# 3K_valdiklis_v1_2.net
KiCad netlist of a schematic drawn in EAGLE
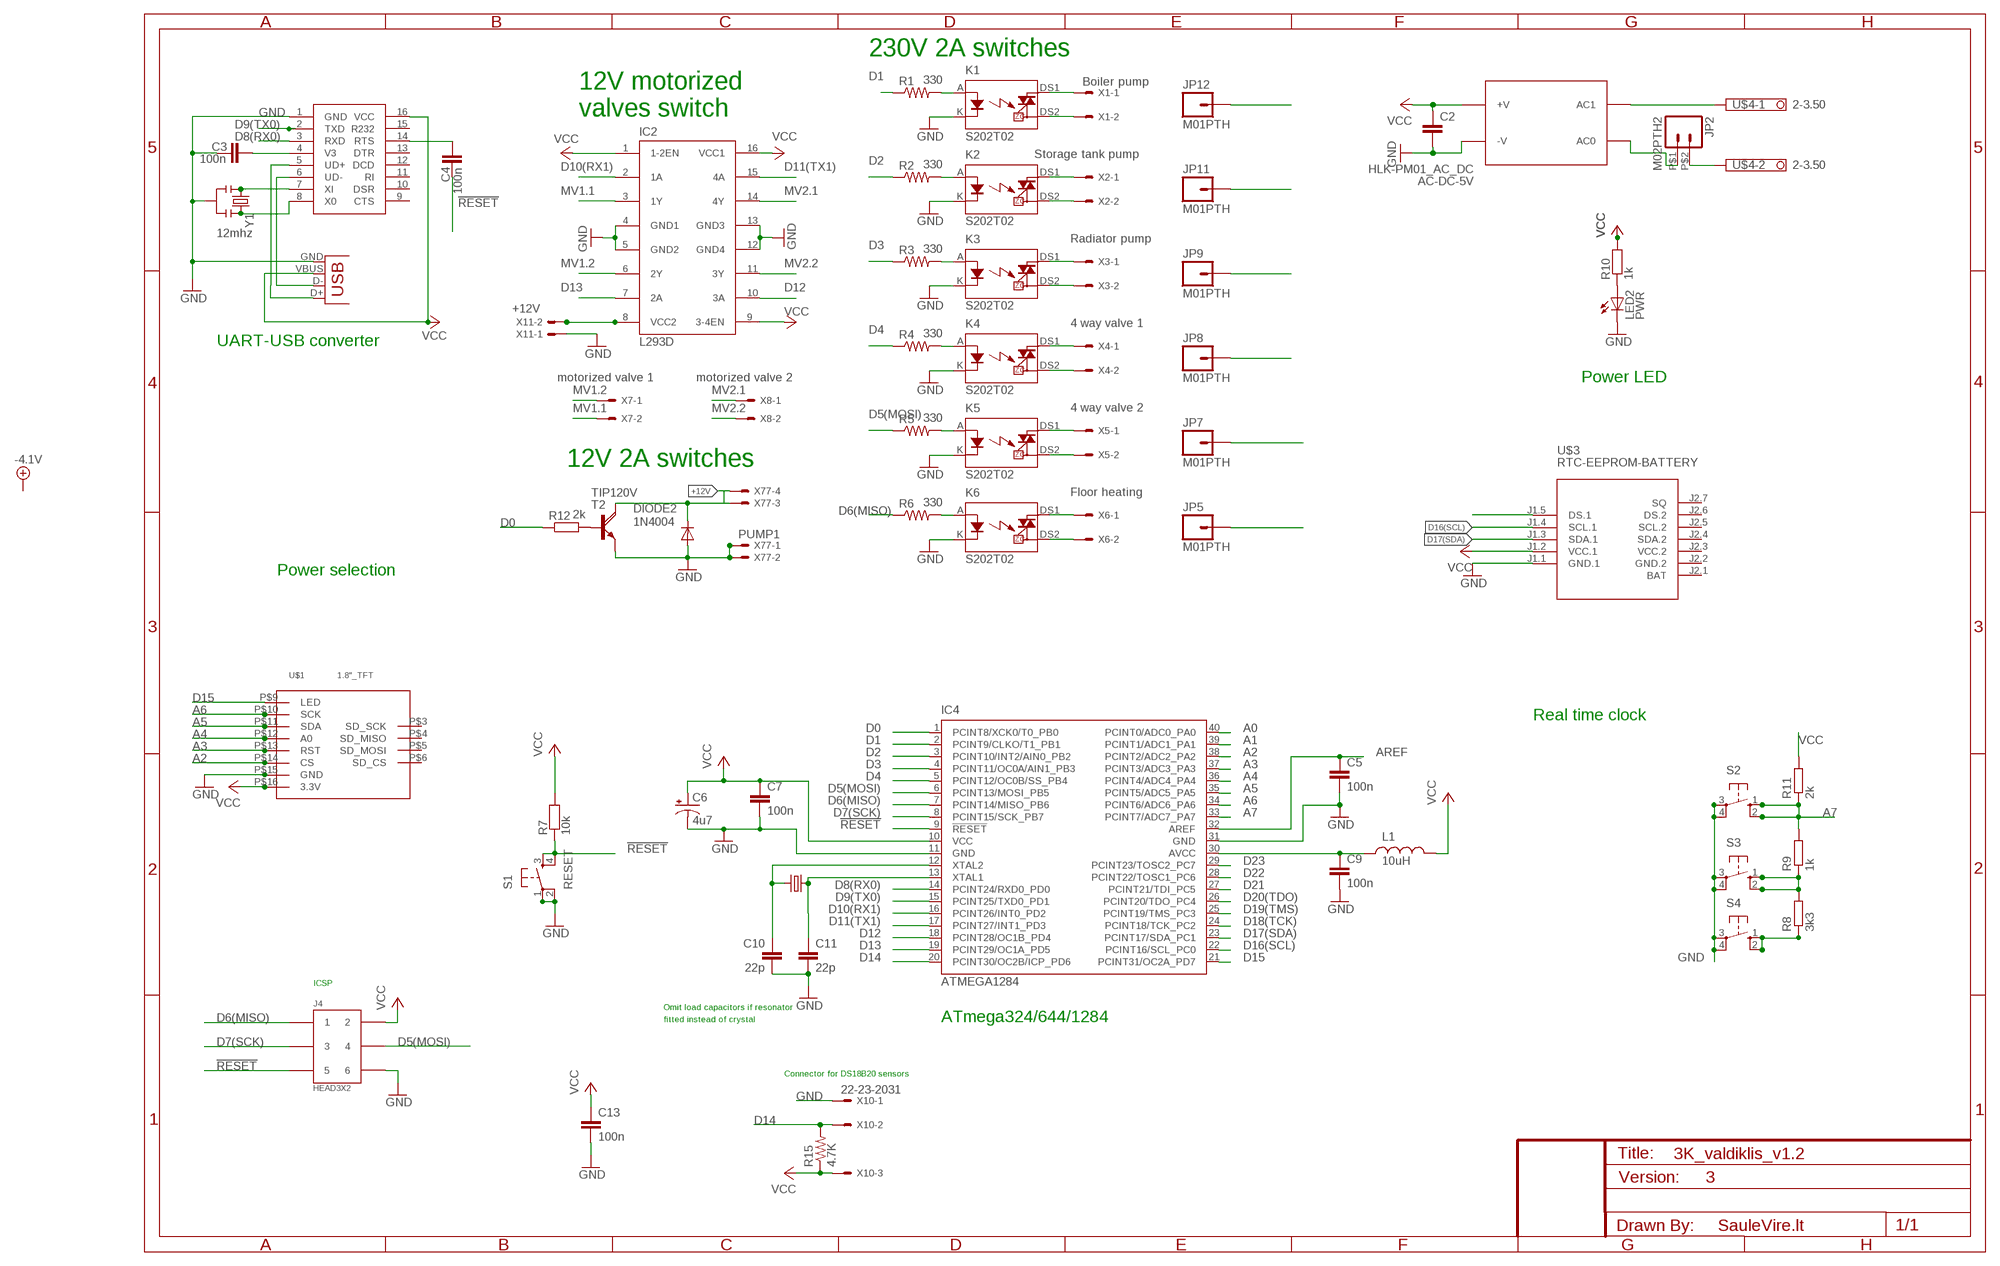
[diagram p0: schematic, sheet 1]

(export (version "E")
  (design (tool "Eeschema 10.0.6"))
  (components
    (comp (ref "AC-DC-5V")
      (value "HLK-PM01_AC_DC")
      (footprint "eagle-import:HLK-PM01_AC_DC")
      (libsource (lib "eagle-import") (part "HLK-PM01_AC_DC"))
    )
    (comp (ref "C2")
      (value "C-EU025-024X044")
      (footprint "eagle-import:C025-024X044")
      (libsource (lib "eagle-import") (part "C-EU025-024X044"))
    )
    (comp (ref "C3")
      (value "100n")
      (footprint "eagle-import:CAP-PTH-SMALL")
      (libsource (lib "eagle-import") (part "CAPPTH"))
    )
    (comp (ref "C4")
      (value "100n")
      (footprint "eagle-import:CAP-PTH-SMALL")
      (libsource (lib "eagle-import") (part "CAPPTH"))
    )
    (comp (ref "C5")
      (value "100n")
      (footprint "eagle-import:CAP-PTH-SMALL")
      (libsource (lib "eagle-import") (part "CAPPTH"))
    )
    (comp (ref "C6")
      (value "4u7")
      (footprint "eagle-import:CPOL-RADIAL-10UF-25V")
      (libsource (lib "eagle-import") (part "CAP_POLPTH2"))
    )
    (comp (ref "C7")
      (value "100n")
      (footprint "eagle-import:CAP-PTH-SMALL")
      (libsource (lib "eagle-import") (part "CAPPTH"))
    )
    (comp (ref "C9")
      (value "100n")
      (footprint "eagle-import:CAP-PTH-SMALL")
      (libsource (lib "eagle-import") (part "CAPPTH"))
    )
    (comp (ref "C10")
      (value "22p")
      (footprint "eagle-import:CAP-PTH-SMALL")
      (libsource (lib "eagle-import") (part "CAPPTH"))
    )
    (comp (ref "C11")
      (value "22p")
      (footprint "eagle-import:CAP-PTH-SMALL")
      (libsource (lib "eagle-import") (part "CAPPTH"))
    )
    (comp (ref "C13")
      (value "100n")
      (footprint "eagle-import:CAP-PTH-SMALL")
      (libsource (lib "eagle-import") (part "CAPPTH"))
    )
    (comp (ref "DIODE2")
      (value "1N4004")
      (footprint "eagle-import:DO41-10")
      (libsource (lib "eagle-import") (part "1N4004"))
    )
    (comp (ref "IC2")
      (value "L293D")
      (footprint "eagle-import:DIL16")
      (libsource (lib "eagle-import") (part "L293D"))
    )
    (comp (ref "IC4")
      (value "ATMEGA1284")
      (footprint "eagle-import:DIL40")
      (fields (field (name "MPN") "ATMEGA644-20PU"))
      (libsource (lib "eagle-import") (part "ATMEGA644-PU20"))
    )
    (comp (ref "J4")
      (value "HEAD3X2")
      (footprint "eagle-import:HEAD3X2")
      (libsource (lib "eagle-import") (part "HEAD3X2"))
    )
    (comp (ref "JP2")
      (value "M02PTH2")
      (footprint "eagle-import:1X02_BIG")
      (libsource (lib "eagle-import") (part "M02PTH2"))
    )
    (comp (ref "JP3")
      (value "USB-B")
      (footprint "eagle-import:USB-B-PTH")
      (libsource (lib "eagle-import") (part "USBPTH"))
    )
    (comp (ref "JP5")
      (value "M01PTH")
      (footprint "eagle-import:1X01")
      (libsource (lib "eagle-import") (part "M01PTH"))
    )
    (comp (ref "JP7")
      (value "M01PTH")
      (footprint "eagle-import:1X01")
      (libsource (lib "eagle-import") (part "M01PTH"))
    )
    (comp (ref "JP8")
      (value "M01PTH")
      (footprint "eagle-import:1X01")
      (libsource (lib "eagle-import") (part "M01PTH"))
    )
    (comp (ref "JP9")
      (value "M01PTH")
      (footprint "eagle-import:1X01")
      (libsource (lib "eagle-import") (part "M01PTH"))
    )
    (comp (ref "JP11")
      (value "M01PTH")
      (footprint "eagle-import:1X01")
      (libsource (lib "eagle-import") (part "M01PTH"))
    )
    (comp (ref "JP12")
      (value "M01PTH")
      (footprint "eagle-import:1X01")
      (libsource (lib "eagle-import") (part "M01PTH"))
    )
    (comp (ref "K1")
      (value "S202T02")
      (footprint "eagle-import:S202T02")
      (libsource (lib "eagle-import") (part "S202T02"))
    )
    (comp (ref "K2")
      (value "S202T02")
      (footprint "eagle-import:S202T02")
      (libsource (lib "eagle-import") (part "S202T02"))
    )
    (comp (ref "K3")
      (value "S202T02")
      (footprint "eagle-import:S202T02")
      (libsource (lib "eagle-import") (part "S202T02"))
    )
    (comp (ref "K4")
      (value "S202T02")
      (footprint "eagle-import:S202T02")
      (libsource (lib "eagle-import") (part "S202T02"))
    )
    (comp (ref "K5")
      (value "S202T02")
      (footprint "eagle-import:S202T02")
      (libsource (lib "eagle-import") (part "S202T02"))
    )
    (comp (ref "K6")
      (value "S202T02")
      (footprint "eagle-import:S202T02")
      (libsource (lib "eagle-import") (part "S202T02"))
    )
    (comp (ref "L1")
      (value "10uH")
      (footprint "eagle-import:RES-AXIAL-0.4")
      (libsource (lib "eagle-import") (part "INDUCTOR0.4{dblquote}-AXIAL"))
    )
    (comp (ref "LED2")
      (value "PWR")
      (footprint "eagle-import:LED3MM")
      (libsource (lib "eagle-import") (part "LED3MM"))
    )
    (comp (ref "R1")
      (value "330")
      (footprint "eagle-import:0207_10")
      (libsource (lib "eagle-import") (part "resistor-1_R-US_0207/10"))
    )
    (comp (ref "R2")
      (value "330")
      (footprint "eagle-import:0207_10")
      (libsource (lib "eagle-import") (part "resistor-1_R-US_0207/10"))
    )
    (comp (ref "R3")
      (value "330")
      (footprint "eagle-import:0207_10")
      (libsource (lib "eagle-import") (part "resistor-1_R-US_0207/10"))
    )
    (comp (ref "R4")
      (value "330")
      (footprint "eagle-import:0207_10")
      (libsource (lib "eagle-import") (part "resistor-1_R-US_0207/10"))
    )
    (comp (ref "R5")
      (value "330")
      (footprint "eagle-import:0207_10")
      (libsource (lib "eagle-import") (part "resistor-1_R-US_0207/10"))
    )
    (comp (ref "R6")
      (value "330")
      (footprint "eagle-import:0207_10")
      (libsource (lib "eagle-import") (part "resistor-1_R-US_0207/10"))
    )
    (comp (ref "R7")
      (value "10k")
      (footprint "eagle-import:RES-AXIAL-0.4")
      (libsource (lib "eagle-import") (part "RESISTOR"))
    )
    (comp (ref "R8")
      (value "3k3")
      (footprint "eagle-import:0207_10")
      (libsource (lib "eagle-import") (part "R-EU_0207/10"))
    )
    (comp (ref "R9")
      (value "1k")
      (footprint "eagle-import:0207_10")
      (libsource (lib "eagle-import") (part "R-EU_0207/10"))
    )
    (comp (ref "R10")
      (value "1k")
      (footprint "eagle-import:RES-AXIAL-0.4")
      (libsource (lib "eagle-import") (part "RESISTOR"))
    )
    (comp (ref "R11")
      (value "2k")
      (footprint "eagle-import:0207_10")
      (libsource (lib "eagle-import") (part "R-EU_0207/10"))
    )
    (comp (ref "R12")
      (value "2k")
      (footprint "eagle-import:0207_10")
      (libsource (lib "eagle-import") (part "R-EU_0207/10"))
    )
    (comp (ref "R15")
      (value "4.7K")
      (footprint "eagle-import:0207_10")
      (libsource (lib "eagle-import") (part "R-US_0207/10"))
    )
    (comp (ref "S1")
      (value "RESET")
      (footprint "eagle-import:TACTILE-PTH")
      (libsource (lib "eagle-import") (part "TAC_SWITCHPTH"))
    )
    (comp (ref "S2")
      (value "10-XX")
      (footprint "eagle-import:B3F-10XX")
      (fields (field (name "MPN") "B3F-1000"))
      (libsource (lib "eagle-import") (part "10-XX"))
    )
    (comp (ref "S3")
      (value "10-XX")
      (footprint "eagle-import:B3F-10XX")
      (fields (field (name "MPN") "B3F-1000"))
      (libsource (lib "eagle-import") (part "10-XX"))
    )
    (comp (ref "S4")
      (value "10-XX")
      (footprint "eagle-import:B3F-10XX")
      (fields (field (name "MPN") "B3F-1000"))
      (libsource (lib "eagle-import") (part "10-XX"))
    )
    (comp (ref "T2")
      (value "TIP120V")
      (footprint "eagle-import:TO220AV")
      (libsource (lib "eagle-import") (part "TIP120V"))
    )
    (comp (ref "U$1")
      (value "1.8\"_TFT")
      (footprint "eagle-import:1.8__TFT")
      (libsource (lib "eagle-import") (part "1.8{dblquote}_TFT"))
    )
    (comp (ref "U$2")
      (value "CH340G")
      (footprint "eagle-import:SO016")
      (libsource (lib "eagle-import") (part "CH340G"))
    )
    (comp (ref "U$3")
      (value "RTC-EEPROM-BATTERY")
      (footprint "eagle-import:RTC_EEPROM_BATTERY")
      (libsource (lib "eagle-import") (part "RTC-EEPROM-BATTERY"))
    )
    (comp (ref "U$4")
      (value "2-3.50")
      (footprint "eagle-import:2-3.50")
      (libsource (lib "eagle-import") (part "2-3.50"))
    )
    (comp (ref "X1")
      (value "Boiler pump")
      (footprint "eagle-import:22-23-2021")
      (fields (field (name "MF") "MOLEX") (field (name "MPN") "22-23-2021"))
      (libsource (lib "eagle-import") (part "22-23-2021"))
    )
    (comp (ref "X2")
      (value "Storage tank pump")
      (footprint "eagle-import:22-23-2021")
      (fields (field (name "MF") "MOLEX") (field (name "MPN") "22-23-2021"))
      (libsource (lib "eagle-import") (part "22-23-2021"))
    )
    (comp (ref "X3")
      (value "Radiator pump")
      (footprint "eagle-import:22-23-2021")
      (fields (field (name "MF") "MOLEX") (field (name "MPN") "22-23-2021"))
      (libsource (lib "eagle-import") (part "22-23-2021"))
    )
    (comp (ref "X4")
      (value "4 way valve 1")
      (footprint "eagle-import:22-23-2021")
      (fields (field (name "MF") "MOLEX") (field (name "MPN") "22-23-2021"))
      (libsource (lib "eagle-import") (part "22-23-2021"))
    )
    (comp (ref "X5")
      (value "4 way valve 2")
      (footprint "eagle-import:22-23-2021")
      (fields (field (name "MF") "MOLEX") (field (name "MPN") "22-23-2021"))
      (libsource (lib "eagle-import") (part "22-23-2021"))
    )
    (comp (ref "X6")
      (value "Floor heating")
      (footprint "eagle-import:22-23-2021")
      (fields (field (name "MF") "MOLEX") (field (name "MPN") "22-23-2021"))
      (libsource (lib "eagle-import") (part "22-23-2021"))
    )
    (comp (ref "X7")
      (value "motorized valve 1")
      (footprint "eagle-import:22-23-2021")
      (fields (field (name "MF") "MOLEX") (field (name "MPN") "22-23-2021"))
      (libsource (lib "eagle-import") (part "22-23-2021"))
    )
    (comp (ref "X8")
      (value "motorized valve 2")
      (footprint "eagle-import:22-23-2021")
      (fields (field (name "MF") "MOLEX") (field (name "MPN") "22-23-2021"))
      (libsource (lib "eagle-import") (part "22-23-2021"))
    )
    (comp (ref "X9")
      (value "16MHz")
      (footprint "eagle-import:HC49US")
      (libsource (lib "eagle-import") (part "CRYSTALHC49US"))
    )
    (comp (ref "X10")
      (value "22-23-2031")
      (footprint "eagle-import:22-23-2031")
      (fields (field (name "MF") "MOLEX"))
      (libsource (lib "eagle-import") (part "22-23-2031"))
    )
    (comp (ref "X11")
      (value "+12V")
      (footprint "eagle-import:22-23-2021")
      (fields (field (name "MF") "MOLEX") (field (name "MPN") "22-23-2021"))
      (libsource (lib "eagle-import") (part "22-23-2021"))
    )
    (comp (ref "X77")
      (value "PUMP1")
      (footprint "eagle-import:22-23-2041")
      (fields (field (name "MF") "MOLEX") (field (name "MPN") "22-23-2041"))
      (libsource (lib "eagle-import") (part "22-23-2041"))
    )
    (comp (ref "Y1")
      (value "12mhz")
      (footprint "eagle-import:RESONATOR-PTH")
      (libsource (lib "eagle-import") (part "RESONATORPTH"))
    )
  )
  (nets
    (net (code "1") (name "+12V") (class "Default")
      (node (ref "DIODE2") (pin "C") (pinfunction "C_C") (pintype "passive"))
      (node (ref "T2") (pin "C") (pinfunction "C_C") (pintype "passive"))
      (node (ref "X77") (pin "3") (pinfunction "S_3") (pintype "passive"))
      (node (ref "X77") (pin "4") (pinfunction "S_4") (pintype "passive"))
    )
    (net (code "3") (name "/A0") (class "Default")
      (node (ref "IC4") (pin "40") (pinfunction "PCINT0/ADC0_PA0_40") (pintype "bidirectional"))
    )
    (net (code "4") (name "/A1") (class "Default")
      (node (ref "IC4") (pin "39") (pinfunction "PCINT1/ADC1_PA1_39") (pintype "bidirectional"))
    )
    (net (code "5") (name "/A2") (class "Default")
      (node (ref "IC4") (pin "38") (pinfunction "PCINT2/ADC2_PA2_38") (pintype "bidirectional"))
      (node (ref "U$1") (pin "P$14") (pinfunction "CS_P$14") (pintype "bidirectional"))
    )
    (net (code "6") (name "/A3") (class "Default")
      (node (ref "IC4") (pin "37") (pinfunction "PCINT3/ADC3_PA3_37") (pintype "bidirectional"))
      (node (ref "U$1") (pin "P$13") (pinfunction "RST_P$13") (pintype "bidirectional"))
    )
    (net (code "7") (name "/A4") (class "Default")
      (node (ref "IC4") (pin "36") (pinfunction "PCINT4/ADC4_PA4_36") (pintype "bidirectional"))
      (node (ref "U$1") (pin "P$12") (pinfunction "A0_P$12") (pintype "bidirectional"))
    )
    (net (code "8") (name "/A5") (class "Default")
      (node (ref "IC4") (pin "35") (pinfunction "PCINT5/ADC5_PA5_35") (pintype "bidirectional"))
      (node (ref "U$1") (pin "P$11") (pinfunction "SDA_P$11") (pintype "bidirectional"))
    )
    (net (code "9") (name "/A6") (class "Default")
      (node (ref "IC4") (pin "34") (pinfunction "PCINT6/ADC6_PA6_34") (pintype "bidirectional"))
      (node (ref "U$1") (pin "P$10") (pinfunction "SCK_P$10") (pintype "bidirectional"))
    )
    (net (code "10") (name "/A7") (class "Default")
      (node (ref "IC4") (pin "33") (pinfunction "PCINT7/ADC7_PA7_33") (pintype "bidirectional"))
      (node (ref "R11") (pin "1") (pinfunction "1_1") (pintype "passive"))
      (node (ref "R9") (pin "2") (pinfunction "2_2") (pintype "passive"))
      (node (ref "S2") (pin "1") (pinfunction "S_1") (pintype "passive"))
      (node (ref "S2") (pin "2") (pinfunction "S1_2") (pintype "passive"))
    )
    (net (code "11") (name "/AREF") (class "Default")
      (node (ref "C5") (pin "1") (pinfunction "1_1") (pintype "passive"))
      (node (ref "IC4") (pin "32") (pinfunction "AREF_32") (pintype "passive"))
    )
    (net (code "12") (name "/D0") (class "Default")
      (node (ref "IC4") (pin "1") (pinfunction "PCINT8/XCK0/T0_PB0_1") (pintype "bidirectional"))
      (node (ref "R12") (pin "1") (pinfunction "1_1") (pintype "passive"))
    )
    (net (code "13") (name "/D1") (class "Default")
      (node (ref "IC4") (pin "2") (pinfunction "PCINT9/CLKO/T1_PB1_2") (pintype "bidirectional"))
      (node (ref "R1") (pin "1") (pinfunction "1_1") (pintype "passive"))
    )
    (net (code "14") (name "/D2") (class "Default")
      (node (ref "IC4") (pin "3") (pinfunction "PCINT10/INT2/AIN0_PB2_3") (pintype "bidirectional"))
      (node (ref "R2") (pin "1") (pinfunction "1_1") (pintype "passive"))
    )
    (net (code "15") (name "/D3") (class "Default")
      (node (ref "IC4") (pin "4") (pinfunction "PCINT11/OC0A/AIN1_PB3_4") (pintype "bidirectional"))
      (node (ref "R3") (pin "1") (pinfunction "1_1") (pintype "passive"))
    )
    (net (code "16") (name "/D4") (class "Default")
      (node (ref "IC4") (pin "5") (pinfunction "PCINT12/OC0B/SS_PB4_5") (pintype "bidirectional"))
      (node (ref "R4") (pin "1") (pinfunction "1_1") (pintype "passive"))
    )
    (net (code "17") (name "/D5(MOSI)") (class "Default")
      (node (ref "IC4") (pin "6") (pinfunction "PCINT13/MOSI_PB5_6") (pintype "bidirectional"))
      (node (ref "J4") (pin "4") (pinfunction "4_4") (pintype "passive"))
      (node (ref "R5") (pin "1") (pinfunction "1_1") (pintype "passive"))
    )
    (net (code "18") (name "/D6(MISO)") (class "Default")
      (node (ref "IC4") (pin "7") (pinfunction "PCINT14/MISO_PB6_7") (pintype "bidirectional"))
      (node (ref "J4") (pin "1") (pinfunction "1_1") (pintype "passive"))
      (node (ref "R6") (pin "1") (pinfunction "1_1") (pintype "passive"))
    )
    (net (code "19") (name "/D7(SCK)") (class "Default")
      (node (ref "IC4") (pin "8") (pinfunction "PCINT15/SCK_PB7_8") (pintype "bidirectional"))
      (node (ref "J4") (pin "3") (pinfunction "3_3") (pintype "passive"))
    )
    (net (code "20") (name "/D8(RX0)") (class "Default")
      (node (ref "IC4") (pin "14") (pinfunction "PCINT24/RXD0_PD0_14") (pintype "bidirectional"))
      (node (ref "U$2") (pin "3") (pinfunction "RXD_3") (pintype "bidirectional"))
    )
    (net (code "21") (name "/D9(TX0)") (class "Default")
      (node (ref "IC4") (pin "15") (pinfunction "PCINT25/TXD0_PD1_15") (pintype "bidirectional"))
      (node (ref "U$2") (pin "2") (pinfunction "TXD_2") (pintype "bidirectional"))
    )
    (net (code "22") (name "/D10(RX1)") (class "Default")
      (node (ref "IC2") (pin "2") (pinfunction "1A_2") (pintype "input"))
      (node (ref "IC4") (pin "16") (pinfunction "PCINT26/INT0_PD2_16") (pintype "bidirectional"))
    )
    (net (code "23") (name "/D11(TX1)") (class "Default")
      (node (ref "IC2") (pin "15") (pinfunction "4A_15") (pintype "input"))
      (node (ref "IC4") (pin "17") (pinfunction "PCINT27/INT1_PD3_17") (pintype "bidirectional"))
    )
    (net (code "24") (name "/D12") (class "Default")
      (node (ref "IC2") (pin "10") (pinfunction "3A_10") (pintype "input"))
      (node (ref "IC4") (pin "18") (pinfunction "PCINT28/OC1B_PD4_18") (pintype "bidirectional"))
    )
    (net (code "25") (name "/D13") (class "Default")
      (node (ref "IC2") (pin "7") (pinfunction "2A_7") (pintype "input"))
      (node (ref "IC4") (pin "19") (pinfunction "PCINT29/OC1A_PD5_19") (pintype "bidirectional"))
    )
    (net (code "26") (name "/D14") (class "Default")
      (node (ref "IC4") (pin "20") (pinfunction "PCINT30/OC2B/ICP_PD6_20") (pintype "bidirectional"))
      (node (ref "R15") (pin "2") (pinfunction "2_2") (pintype "passive"))
      (node (ref "X10") (pin "2") (pinfunction "S_2") (pintype "passive"))
    )
    (net (code "27") (name "/D15") (class "Default")
      (node (ref "IC4") (pin "21") (pinfunction "PCINT31/OC2A_PD7_21") (pintype "bidirectional"))
      (node (ref "U$1") (pin "P$9") (pinfunction "LED_P$9") (pintype "bidirectional"))
    )
    (net (code "28") (name "/D18(TCK)") (class "Default")
      (node (ref "IC4") (pin "24") (pinfunction "PCINT18/TCK_PC2_24") (pintype "bidirectional"))
    )
    (net (code "29") (name "/D19(TMS)") (class "Default")
      (node (ref "IC4") (pin "25") (pinfunction "PCINT19/TMS_PC3_25") (pintype "bidirectional"))
    )
    (net (code "30") (name "/D20(TDO)") (class "Default")
      (node (ref "IC4") (pin "26") (pinfunction "PCINT20/TDO_PC4_26") (pintype "bidirectional"))
    )
    (net (code "31") (name "/D21") (class "Default")
      (node (ref "IC4") (pin "27") (pinfunction "PCINT21/TDI_PC5_27") (pintype "bidirectional"))
    )
    (net (code "32") (name "/D22") (class "Default")
      (node (ref "IC4") (pin "28") (pinfunction "PCINT22/TOSC1_PC6_28") (pintype "bidirectional"))
    )
    (net (code "33") (name "/D23") (class "Default")
      (node (ref "IC4") (pin "29") (pinfunction "PCINT23/TOSC2_PC7_29") (pintype "bidirectional"))
    )
    (net (code "34") (name "/GND.2") (class "Default")
      (node (ref "U$3") (pin "J2.2") (pinfunction "GND.2_J2.2") (pintype "power_in"))
    )
    (net (code "35") (name "/MV1.1") (class "Default")
      (node (ref "IC2") (pin "3") (pinfunction "1Y_3") (pintype "output"))
      (node (ref "X7") (pin "2") (pinfunction "S_2") (pintype "passive"))
    )
    (net (code "36") (name "/MV1.2") (class "Default")
      (node (ref "IC2") (pin "6") (pinfunction "2Y_6") (pintype "output"))
      (node (ref "X7") (pin "1") (pinfunction "S_1") (pintype "passive"))
    )
    (net (code "37") (name "/MV2.1") (class "Default")
      (node (ref "IC2") (pin "14") (pinfunction "4Y_14") (pintype "output"))
      (node (ref "X8") (pin "1") (pinfunction "S_1") (pintype "passive"))
    )
    (net (code "38") (name "/MV2.2") (class "Default")
      (node (ref "IC2") (pin "11") (pinfunction "3Y_11") (pintype "output"))
      (node (ref "X8") (pin "2") (pinfunction "S_2") (pintype "passive"))
    )
    (net (code "39") (name "/N$18") (class "Default")
      (node (ref "JP9") (pin "1") (pinfunction "1_1") (pintype "passive"))
      (node (ref "K3") (pin "DS1") (pinfunction "DS1_DS1") (pintype "passive"))
      (node (ref "X3") (pin "1") (pinfunction "S_1") (pintype "passive"))
    )
    (net (code "40") (name "/N$25") (class "Default")
      (node (ref "JP11") (pin "1") (pinfunction "1_1") (pintype "passive"))
      (node (ref "K2") (pin "DS1") (pinfunction "DS1_DS1") (pintype "passive"))
      (node (ref "X2") (pin "1") (pinfunction "S_1") (pintype "passive"))
    )
    (net (code "41") (name "/N$29") (class "Default")
      (node (ref "JP8") (pin "1") (pinfunction "1_1") (pintype "passive"))
      (node (ref "K4") (pin "DS1") (pinfunction "DS1_DS1") (pintype "passive"))
      (node (ref "X4") (pin "1") (pinfunction "S_1") (pintype "passive"))
    )
    (net (code "42") (name "/N$32") (class "Default")
      (node (ref "JP12") (pin "1") (pinfunction "1_1") (pintype "passive"))
      (node (ref "K1") (pin "DS1") (pinfunction "DS1_DS1") (pintype "passive"))
      (node (ref "X1") (pin "1") (pinfunction "S_1") (pintype "passive"))
    )
    (net (code "43") (name "/N$35") (class "Default")
      (node (ref "JP5") (pin "1") (pinfunction "1_1") (pintype "passive"))
      (node (ref "K6") (pin "DS1") (pinfunction "DS1_DS1") (pintype "passive"))
      (node (ref "X6") (pin "1") (pinfunction "S_1") (pintype "passive"))
    )
    (net (code "44") (name "/N$38") (class "Default")
      (node (ref "JP7") (pin "1") (pinfunction "1_1") (pintype "passive"))
      (node (ref "K5") (pin "DS1") (pinfunction "DS1_DS1") (pintype "passive"))
      (node (ref "X5") (pin "1") (pinfunction "S_1") (pintype "passive"))
    )
    (net (code "45") (name "/VCC.2") (class "Default")
      (node (ref "U$3") (pin "J2.3") (pinfunction "VCC.2_J2.3") (pintype "power_in"))
    )
    (net (code "46") (name "/~{RESET}") (class "Default")
      (node (ref "C4") (pin "1") (pinfunction "1_1") (pintype "passive"))
      (node (ref "IC4") (pin "9") (pinfunction "~{RESET}_9") (pintype "input"))
      (node (ref "J4") (pin "5") (pinfunction "5_5") (pintype "passive"))
      (node (ref "R7") (pin "P$1") (pinfunction "1_P$1") (pintype "passive"))
      (node (ref "S1") (pin "3") (pinfunction "3_3") (pintype "passive"))
      (node (ref "S1") (pin "4") (pinfunction "4_4") (pintype "passive"))
    )
    (net (code "47") (name "D16(SCL)") (class "Default")
      (node (ref "IC4") (pin "22") (pinfunction "PCINT16/SCL_PC0_22") (pintype "bidirectional"))
      (node (ref "U$3") (pin "J1.4") (pinfunction "SCL.1_J1.4") (pintype "bidirectional"))
    )
    (net (code "48") (name "D17(SDA)") (class "Default")
      (node (ref "IC4") (pin "23") (pinfunction "PCINT17/SDA_PC1_23") (pintype "bidirectional"))
      (node (ref "U$3") (pin "J1.3") (pinfunction "SDA.1_J1.3") (pintype "bidirectional"))
    )
    (net (code "49") (name "GND") (class "Default")
      (node (ref "AC-DC-5V") (pin "-V") (pinfunction "-V_-V") (pintype "output"))
      (node (ref "C10") (pin "2") (pinfunction "2_2") (pintype "passive"))
      (node (ref "C11") (pin "2") (pinfunction "2_2") (pintype "passive"))
      (node (ref "C13") (pin "2") (pinfunction "2_2") (pintype "passive"))
      (node (ref "C2") (pin "2") (pinfunction "2_2") (pintype "passive"))
      (node (ref "C3") (pin "1") (pinfunction "1_1") (pintype "passive"))
      (node (ref "C5") (pin "2") (pinfunction "2_2") (pintype "passive"))
      (node (ref "C6") (pin "2") (pinfunction "-_2") (pintype "passive"))
      (node (ref "C7") (pin "2") (pinfunction "2_2") (pintype "passive"))
      (node (ref "C9") (pin "2") (pinfunction "2_2") (pintype "passive"))
      (node (ref "DIODE2") (pin "A") (pinfunction "A_A") (pintype "passive"))
      (node (ref "IC2") (pin "12") (pinfunction "GND4_12") (pintype "power_in"))
      (node (ref "IC2") (pin "13") (pinfunction "GND3_13") (pintype "power_in"))
      (node (ref "IC2") (pin "4") (pinfunction "GND1_4") (pintype "power_in"))
      (node (ref "IC2") (pin "5") (pinfunction "GND2_5") (pintype "power_in"))
      (node (ref "IC4") (pin "11") (pinfunction "GND_11") (pintype "power_in"))
      (node (ref "IC4") (pin "31") (pinfunction "GND_31") (pintype "power_in"))
      (node (ref "J4") (pin "6") (pinfunction "6_6") (pintype "passive"))
      (node (ref "JP3") (pin "GND") (pinfunction "GND_GND") (pintype "bidirectional"))
      (node (ref "K1") (pin "K") (pinfunction "K_K") (pintype "passive"))
      (node (ref "K2") (pin "K") (pinfunction "K_K") (pintype "passive"))
      (node (ref "K3") (pin "K") (pinfunction "K_K") (pintype "passive"))
      (node (ref "K4") (pin "K") (pinfunction "K_K") (pintype "passive"))
      (node (ref "K5") (pin "K") (pinfunction "K_K") (pintype "passive"))
      (node (ref "K6") (pin "K") (pinfunction "K_K") (pintype "passive"))
      (node (ref "LED2") (pin "K") (pinfunction "C_K") (pintype "passive"))
      (node (ref "S1") (pin "1") (pinfunction "1_1") (pintype "passive"))
      (node (ref "S1") (pin "2") (pinfunction "2_2") (pintype "passive"))
      (node (ref "S2") (pin "3") (pinfunction "P_3") (pintype "passive"))
      (node (ref "S2") (pin "4") (pinfunction "P1_4") (pintype "passive"))
      (node (ref "S3") (pin "3") (pinfunction "P_3") (pintype "passive"))
      (node (ref "S3") (pin "4") (pinfunction "P1_4") (pintype "passive"))
      (node (ref "S4") (pin "3") (pinfunction "P_3") (pintype "passive"))
      (node (ref "S4") (pin "4") (pinfunction "P1_4") (pintype "passive"))
      (node (ref "T2") (pin "E") (pinfunction "E_E") (pintype "passive"))
      (node (ref "U$1") (pin "P$15") (pinfunction "GND_P$15") (pintype "bidirectional"))
      (node (ref "U$2") (pin "1") (pinfunction "GND_1") (pintype "bidirectional"))
      (node (ref "U$3") (pin "J1.1") (pinfunction "GND.1_J1.1") (pintype "power_in"))
      (node (ref "X10") (pin "1") (pinfunction "S_1") (pintype "passive"))
      (node (ref "X11") (pin "1") (pinfunction "S_1") (pintype "passive"))
      (node (ref "X77") (pin "1") (pinfunction "S_1") (pintype "passive"))
      (node (ref "X77") (pin "2") (pinfunction "S_2") (pintype "passive"))
      (node (ref "Y1") (pin "2") (pinfunction "2_2") (pintype "passive"))
    )
    (net (code "50") (name "Net-(IC2-VCC2)") (class "Default")
      (node (ref "IC2") (pin "8") (pinfunction "VCC2_8") (pintype "power_in"))
      (node (ref "X11") (pin "2") (pinfunction "S_2") (pintype "passive"))
    )
    (net (code "51") (name "Net-(IC4-AVCC)") (class "Default")
      (node (ref "C9") (pin "1") (pinfunction "1_1") (pintype "passive"))
      (node (ref "IC4") (pin "30") (pinfunction "AVCC_30") (pintype "power_in"))
      (node (ref "L1") (pin "P$1") (pinfunction "1_P$1") (pintype "passive"))
    )
    (net (code "52") (name "Net-(IC4-XTAL1)") (class "Default")
      (node (ref "C11") (pin "1") (pinfunction "1_1") (pintype "passive"))
      (node (ref "IC4") (pin "13") (pinfunction "XTAL1_13") (pintype "input"))
      (node (ref "X9") (pin "1") (pinfunction "1_1") (pintype "passive"))
    )
    (net (code "53") (name "Net-(IC4-XTAL2)") (class "Default")
      (node (ref "C10") (pin "1") (pinfunction "1_1") (pintype "passive"))
      (node (ref "IC4") (pin "12") (pinfunction "XTAL2_12") (pintype "output"))
      (node (ref "X9") (pin "2") (pinfunction "2_2") (pintype "passive"))
    )
    (net (code "54") (name "Net-(JP2-1)") (class "Default")
      (node (ref "AC-DC-5V") (pin "AC0") (pinfunction "AC0_AC0") (pintype "power_in"))
      (node (ref "JP2") (pin "P$1") (pinfunction "1_P$1") (pintype "passive"))
    )
    (net (code "55") (name "Net-(JP2-2)") (class "Default")
      (node (ref "JP2") (pin "P$2") (pinfunction "2_P$2") (pintype "passive"))
      (node (ref "U$4") (pin "2") (pinfunction "K_2") (pintype "passive"))
    )
    (net (code "56") (name "Net-(K1-PadA)") (class "Default")
      (node (ref "K1") (pin "A") (pinfunction "A_A") (pintype "passive"))
      (node (ref "R1") (pin "2") (pinfunction "2_2") (pintype "passive"))
    )
    (net (code "57") (name "Net-(K2-PadA)") (class "Default")
      (node (ref "K2") (pin "A") (pinfunction "A_A") (pintype "passive"))
      (node (ref "R2") (pin "2") (pinfunction "2_2") (pintype "passive"))
    )
    (net (code "58") (name "Net-(K3-PadA)") (class "Default")
      (node (ref "K3") (pin "A") (pinfunction "A_A") (pintype "passive"))
      (node (ref "R3") (pin "2") (pinfunction "2_2") (pintype "passive"))
    )
    (net (code "59") (name "Net-(K4-PadA)") (class "Default")
      (node (ref "K4") (pin "A") (pinfunction "A_A") (pintype "passive"))
      (node (ref "R4") (pin "2") (pinfunction "2_2") (pintype "passive"))
    )
    (net (code "60") (name "Net-(K5-PadA)") (class "Default")
      (node (ref "K5") (pin "A") (pinfunction "A_A") (pintype "passive"))
      (node (ref "R5") (pin "2") (pinfunction "2_2") (pintype "passive"))
    )
    (net (code "61") (name "Net-(K6-PadA)") (class "Default")
      (node (ref "K6") (pin "A") (pinfunction "A_A") (pintype "passive"))
      (node (ref "R6") (pin "2") (pinfunction "2_2") (pintype "passive"))
    )
    (net (code "62") (name "Net-(R10-1)") (class "Default")
      (node (ref "LED2") (pin "A") (pinfunction "A_A") (pintype "passive"))
      (node (ref "R10") (pin "P$1") (pinfunction "1_P$1") (pintype "passive"))
    )
    (net (code "63") (name "Net-(R12-Pad2)") (class "Default")
      (node (ref "R12") (pin "2") (pinfunction "2_2") (pintype "passive"))
      (node (ref "T2") (pin "B") (pinfunction "B_B") (pintype "passive"))
    )
    (net (code "64") (name "Net-(S3-S)") (class "Default")
      (node (ref "R8") (pin "2") (pinfunction "2_2") (pintype "passive"))
      (node (ref "R9") (pin "1") (pinfunction "1_1") (pintype "passive"))
      (node (ref "S3") (pin "1") (pinfunction "S_1") (pintype "passive"))
      (node (ref "S3") (pin "2") (pinfunction "S1_2") (pintype "passive"))
    )
    (net (code "65") (name "Net-(S4-S)") (class "Default")
      (node (ref "R8") (pin "1") (pinfunction "1_1") (pintype "passive"))
      (node (ref "S4") (pin "1") (pinfunction "S_1") (pintype "passive"))
      (node (ref "S4") (pin "2") (pinfunction "S1_2") (pintype "passive"))
    )
    (net (code "66") (name "Net-(U$2-RTS)") (class "Default")
      (node (ref "C4") (pin "2") (pinfunction "2_2") (pintype "passive"))
      (node (ref "U$2") (pin "14") (pinfunction "RTS_14") (pintype "bidirectional"))
    )
    (net (code "67") (name "Net-(U$2-UD+)") (class "Default")
      (node (ref "JP3") (pin "D+") (pinfunction "D+_D+") (pintype "bidirectional"))
      (node (ref "U$2") (pin "5") (pinfunction "UD+_5") (pintype "bidirectional"))
    )
    (net (code "68") (name "Net-(U$2-UD-)") (class "Default")
      (node (ref "JP3") (pin "D-") (pinfunction "D-_D-") (pintype "bidirectional"))
      (node (ref "U$2") (pin "6") (pinfunction "UD-_6") (pintype "bidirectional"))
    )
    (net (code "69") (name "Net-(U$2-V3)") (class "Default")
      (node (ref "C3") (pin "2") (pinfunction "2_2") (pintype "passive"))
      (node (ref "U$2") (pin "4") (pinfunction "V3_4") (pintype "bidirectional"))
    )
    (net (code "70") (name "Net-(U$2-X0)") (class "Default")
      (node (ref "U$2") (pin "8") (pinfunction "X0_8") (pintype "bidirectional"))
      (node (ref "Y1") (pin "3") (pinfunction "3_3") (pintype "passive"))
    )
    (net (code "71") (name "Net-(U$2-XI)") (class "Default")
      (node (ref "U$2") (pin "7") (pinfunction "XI_7") (pintype "bidirectional"))
      (node (ref "Y1") (pin "1") (pinfunction "1_1") (pintype "passive"))
    )
    (net (code "72") (name "Net-(U$4A-K)") (class "Default")
      (node (ref "AC-DC-5V") (pin "AC1") (pinfunction "AC1_AC1") (pintype "power_in"))
      (node (ref "U$4") (pin "1") (pinfunction "K_1") (pintype "passive"))
    )
    (net (code "73") (name "Net-(X1B-S)") (class "Default")
      (node (ref "K1") (pin "DS2") (pinfunction "DS2_DS2") (pintype "passive"))
      (node (ref "X1") (pin "2") (pinfunction "S_2") (pintype "passive"))
    )
    (net (code "74") (name "Net-(X2B-S)") (class "Default")
      (node (ref "K2") (pin "DS2") (pinfunction "DS2_DS2") (pintype "passive"))
      (node (ref "X2") (pin "2") (pinfunction "S_2") (pintype "passive"))
    )
    (net (code "75") (name "Net-(X3B-S)") (class "Default")
      (node (ref "K3") (pin "DS2") (pinfunction "DS2_DS2") (pintype "passive"))
      (node (ref "X3") (pin "2") (pinfunction "S_2") (pintype "passive"))
    )
    (net (code "76") (name "Net-(X4B-S)") (class "Default")
      (node (ref "K4") (pin "DS2") (pinfunction "DS2_DS2") (pintype "passive"))
      (node (ref "X4") (pin "2") (pinfunction "S_2") (pintype "passive"))
    )
    (net (code "77") (name "Net-(X5B-S)") (class "Default")
      (node (ref "K5") (pin "DS2") (pinfunction "DS2_DS2") (pintype "passive"))
      (node (ref "X5") (pin "2") (pinfunction "S_2") (pintype "passive"))
    )
    (net (code "78") (name "Net-(X6B-S)") (class "Default")
      (node (ref "K6") (pin "DS2") (pinfunction "DS2_DS2") (pintype "passive"))
      (node (ref "X6") (pin "2") (pinfunction "S_2") (pintype "passive"))
    )
    (net (code "79") (name "VCC") (class "Default")
      (node (ref "AC-DC-5V") (pin "+V") (pinfunction "+V_+V") (pintype "output"))
      (node (ref "C13") (pin "1") (pinfunction "1_1") (pintype "passive"))
      (node (ref "C2") (pin "1") (pinfunction "1_1") (pintype "passive"))
      (node (ref "C6") (pin "1") (pinfunction "+_1") (pintype "passive"))
      (node (ref "C7") (pin "1") (pinfunction "1_1") (pintype "passive"))
      (node (ref "IC2") (pin "1") (pinfunction "1-2EN_1") (pintype "input"))
      (node (ref "IC2") (pin "16") (pinfunction "VCC1_16") (pintype "power_in"))
      (node (ref "IC2") (pin "9") (pinfunction "3-4EN_9") (pintype "input"))
      (node (ref "IC4") (pin "10") (pinfunction "VCC_10") (pintype "power_in"))
      (node (ref "J4") (pin "2") (pinfunction "2_2") (pintype "passive"))
      (node (ref "JP3") (pin "VBUS") (pinfunction "VBUS_VBUS") (pintype "bidirectional"))
      (node (ref "L1") (pin "P$2") (pinfunction "2_P$2") (pintype "passive"))
      (node (ref "R10") (pin "P$2") (pinfunction "2_P$2") (pintype "passive"))
      (node (ref "R11") (pin "2") (pinfunction "2_2") (pintype "passive"))
      (node (ref "R15") (pin "1") (pinfunction "1_1") (pintype "passive"))
      (node (ref "R7") (pin "P$2") (pinfunction "2_P$2") (pintype "passive"))
      (node (ref "U$1") (pin "P$16") (pinfunction "3.3V_P$16") (pintype "bidirectional"))
      (node (ref "U$2") (pin "16") (pinfunction "VCC_16") (pintype "bidirectional"))
      (node (ref "U$3") (pin "J1.2") (pinfunction "VCC.1_J1.2") (pintype "power_in"))
      (node (ref "X10") (pin "3") (pinfunction "S_3") (pintype "passive"))
    )
    (net (code "80") (name "unconnected-(U$1-SD_CS-PadP$6)") (class "Default")
      (node (ref "U$1") (pin "P$6") (pinfunction "SD_CS_P$6") (pintype "bidirectional"))
    )
    (net (code "81") (name "unconnected-(U$1-SD_MISO-PadP$4)") (class "Default")
      (node (ref "U$1") (pin "P$4") (pinfunction "SD_MISO_P$4") (pintype "bidirectional"))
    )
    (net (code "82") (name "unconnected-(U$1-SD_MOSI-PadP$5)") (class "Default")
      (node (ref "U$1") (pin "P$5") (pinfunction "SD_MOSI_P$5") (pintype "bidirectional"))
    )
    (net (code "83") (name "unconnected-(U$1-SD_SCK-PadP$3)") (class "Default")
      (node (ref "U$1") (pin "P$3") (pinfunction "SD_SCK_P$3") (pintype "bidirectional"))
    )
    (net (code "84") (name "unconnected-(U$2-CTS-Pad9)") (class "Default")
      (node (ref "U$2") (pin "9") (pinfunction "CTS_9") (pintype "bidirectional"))
    )
    (net (code "85") (name "unconnected-(U$2-DCD-Pad12)") (class "Default")
      (node (ref "U$2") (pin "12") (pinfunction "DCD_12") (pintype "bidirectional"))
    )
    (net (code "86") (name "unconnected-(U$2-DSR-Pad10)") (class "Default")
      (node (ref "U$2") (pin "10") (pinfunction "DSR_10") (pintype "bidirectional"))
    )
    (net (code "87") (name "unconnected-(U$2-DTR-Pad13)") (class "Default")
      (node (ref "U$2") (pin "13") (pinfunction "DTR_13") (pintype "bidirectional"))
    )
    (net (code "88") (name "unconnected-(U$2-R232-Pad15)") (class "Default")
      (node (ref "U$2") (pin "15") (pinfunction "R232_15") (pintype "bidirectional"))
    )
    (net (code "89") (name "unconnected-(U$2-RI-Pad11)") (class "Default")
      (node (ref "U$2") (pin "11") (pinfunction "RI_11") (pintype "bidirectional"))
    )
    (net (code "90") (name "unconnected-(U$3-BAT-PadJ2.1)") (class "Default")
      (node (ref "U$3") (pin "J2.1") (pinfunction "BAT_J2.1") (pintype "bidirectional"))
    )
    (net (code "91") (name "unconnected-(U$3-DS.1-PadJ1.5)") (class "Default")
      (node (ref "U$3") (pin "J1.5") (pinfunction "DS.1_J1.5") (pintype "bidirectional"))
    )
    (net (code "92") (name "unconnected-(U$3-DS.2-PadJ2.6)") (class "Default")
      (node (ref "U$3") (pin "J2.6") (pinfunction "DS.2_J2.6") (pintype "bidirectional"))
    )
    (net (code "93") (name "unconnected-(U$3-SCL.2-PadJ2.5)") (class "Default")
      (node (ref "U$3") (pin "J2.5") (pinfunction "SCL.2_J2.5") (pintype "bidirectional"))
    )
    (net (code "94") (name "unconnected-(U$3-SDA.2-PadJ2.4)") (class "Default")
      (node (ref "U$3") (pin "J2.4") (pinfunction "SDA.2_J2.4") (pintype "bidirectional"))
    )
    (net (code "95") (name "unconnected-(U$3-SQ-PadJ2.7)") (class "Default")
      (node (ref "U$3") (pin "J2.7") (pinfunction "SQ_J2.7") (pintype "bidirectional"))
    )
  )
)
